# power2V5.net
KiCad netlist of a schematic drawn in Altium Designer
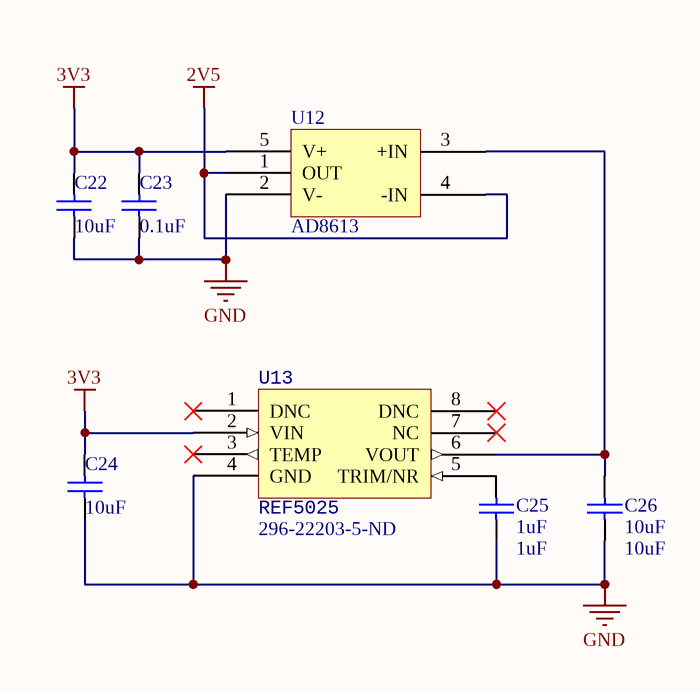
[diagram p0: power2V5.SchDoc]

(export (version "E")
  (design (tool "Eeschema 10.0.6"))
  (components
    (comp (ref "C22")
      (value "10uF")
      (footprint "1608[0603]")
      (description "Capacitor (Semiconductor SIM Model)")
      (fields (field (name "PUBLISHER") "Altium Limited"))
      (libsource (lib "Miscellaneous Devices") (part "Cap Semi"))
    )
    (comp (ref "C23")
      (value "0.1uF")
      (footprint "1608[0603]")
      (description "Capacitor (Semiconductor SIM Model)")
      (fields (field (name "PUBLISHER") "Altium Limited"))
      (libsource (lib "Miscellaneous Devices") (part "Cap Semi"))
    )
    (comp (ref "C24")
      (value "10uF")
      (footprint "1608[0603]")
      (description "Capacitor (Semiconductor SIM Model)")
      (fields (field (name "PUBLISHER") "Altium Limited"))
      (libsource (lib "Miscellaneous Devices") (part "Cap Semi"))
    )
    (comp (ref "C25")
      (value "1uF")
      (footprint "1608[0603]")
      (description "Capacitor (Semiconductor SIM Model)")
      (fields (field (name "ALTIUM_VALUE") "1uF") (field (name "PUBLISHER") "Altium Limited"))
      (libsource (lib "Miscellaneous Devices") (part "Cap Semi"))
    )
    (comp (ref "C26")
      (value "10uF")
      (footprint "1608[0603]")
      (description "Capacitor (Semiconductor SIM Model)")
      (fields (field (name "ALTIUM_VALUE") "10uF") (field (name "PUBLISHER") "Altium Limited"))
      (libsource (lib "Miscellaneous Devices") (part "Cap Semi"))
    )
    (comp (ref "U12")
      (value "AD8613")
      (footprint "SOP-65P200X125-5N")
      (description "Low power, low noise rail-to-rail op-amp.")
      (libsource (lib "PAY") (part "AD8613"))
    )
    (comp (ref "U13")
      (value "REF5025")
      (footprint "SOIC127P500X600-8N")
      (description "Voltage Reference")
      (fields (field (name "SUPPLIER PART NUMBER 1") "296-22203-5-ND"))
      (libsource (lib "heron-general") (part "REF5025"))
    )
  )
  (nets
    (net (code "1") (name "2V5") (class "Default")
      (node (ref "U12") (pin "1") (pinfunction "OUT_1") (pintype "passive"))
      (node (ref "U12") (pin "4") (pinfunction "-IN_4") (pintype "passive"))
    )
    (net (code "2") (name "3V3") (class "Default")
      (node (ref "C22") (pin "2") (pinfunction "2_2") (pintype "passive"))
      (node (ref "C23") (pin "2") (pinfunction "2_2") (pintype "passive"))
      (node (ref "C24") (pin "2") (pinfunction "2_2") (pintype "passive"))
      (node (ref "U12") (pin "5") (pinfunction "V+_5") (pintype "passive"))
      (node (ref "U13") (pin "2") (pinfunction "VIN_2") (pintype "input"))
    )
    (net (code "3") (name "GND") (class "Default")
      (node (ref "C22") (pin "1") (pinfunction "1_1") (pintype "passive"))
      (node (ref "C23") (pin "1") (pinfunction "1_1") (pintype "passive"))
      (node (ref "C24") (pin "1") (pinfunction "1_1") (pintype "passive"))
      (node (ref "C25") (pin "1") (pinfunction "1_1") (pintype "passive"))
      (node (ref "C26") (pin "1") (pinfunction "1_1") (pintype "passive"))
      (node (ref "U12") (pin "2") (pinfunction "V-_2") (pintype "passive"))
      (node (ref "U13") (pin "4") (pinfunction "GND_4") (pintype "power_in"))
    )
    (net (code "4") (name "Net-(U12-+IN)") (class "Default")
      (node (ref "C26") (pin "2") (pinfunction "2_2") (pintype "passive"))
      (node (ref "U12") (pin "3") (pinfunction "+IN_3") (pintype "passive"))
      (node (ref "U13") (pin "6") (pinfunction "VOUT_6") (pintype "output"))
    )
    (net (code "5") (name "Net-(U13-TRIM{slash}NR)") (class "Default")
      (node (ref "C25") (pin "2") (pinfunction "2_2") (pintype "passive"))
      (node (ref "U13") (pin "5") (pinfunction "TRIM/NR_5") (pintype "input"))
    )
    (net (code "6") (name "unconnected-(U13-DNC-Pad1)") (class "Default")
      (node (ref "U13") (pin "1") (pinfunction "DNC_1") (pintype "passive+no_connect"))
    )
    (net (code "7") (name "unconnected-(U13-DNC-Pad8)") (class "Default")
      (node (ref "U13") (pin "8") (pinfunction "DNC_8") (pintype "passive+no_connect"))
    )
    (net (code "8") (name "unconnected-(U13-NC-Pad7)") (class "Default")
      (node (ref "U13") (pin "7") (pinfunction "NC_7") (pintype "passive+no_connect"))
    )
    (net (code "9") (name "unconnected-(U13-TEMP-Pad3)") (class "Default")
      (node (ref "U13") (pin "3") (pinfunction "TEMP_3") (pintype "output+no_connect"))
    )
  )
)
